# System_Power_Schematic.net
KiCad netlist of a schematic drawn in EAGLE
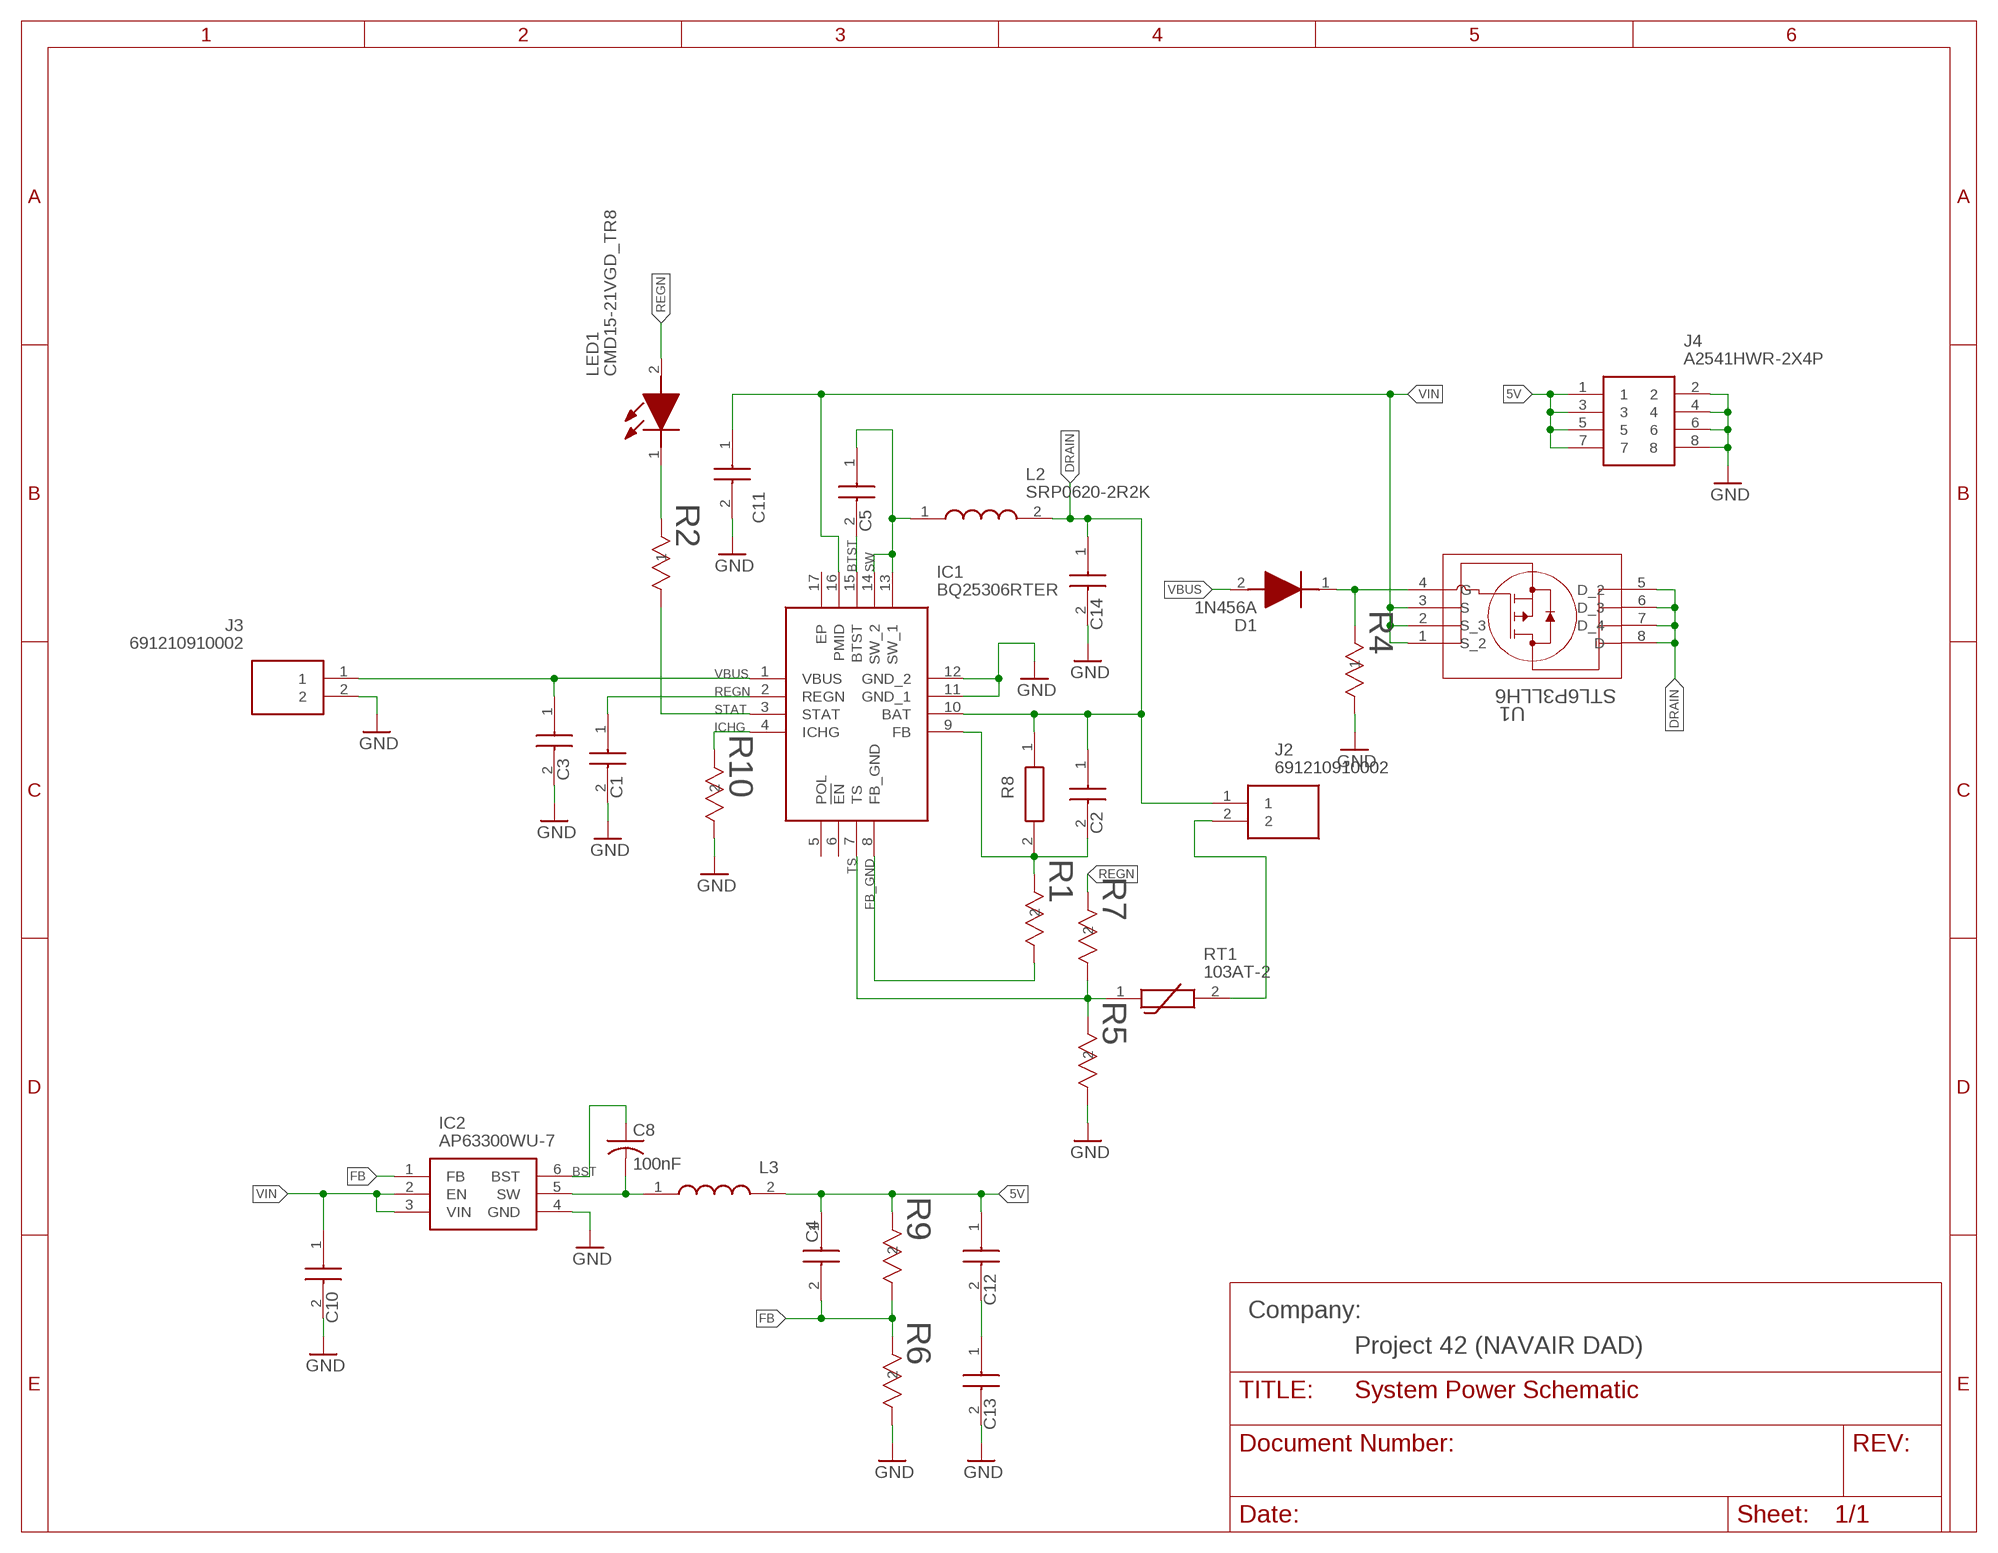
[diagram p0: schematic, sheet 1]

(export (version "E")
  (design (tool "Eeschema 10.0.6"))
  (components
    (comp (ref "C1")
      (value "TMK107ABJ225KA-T")
      (footprint "eagle-import:CAPC1608X90N")
      (fields (field (name "MOUSER_PART_NUMBER") "963-TMK107ABJ225KA-T"))
      (libsource (lib "eagle-import") (part "TMK107ABJ225KA-T"))
    )
    (comp (ref "C2")
      (value "CGA1A2X7R1H471K030BA")
      (footprint "eagle-import:CAPC1608X90N")
      (fields (field (name "MOUSER_PART_NUMBER") "810-CGA1A2X7R1H471KA"))
      (libsource (lib "eagle-import") (part "CGA1A2X7R1H471K030BA"))
    )
    (comp (ref "C3")
      (value "TMK107ABJ225KA-T")
      (footprint "eagle-import:CAPC1608X90N")
      (fields (field (name "MOUSER_PART_NUMBER") "963-TMK107ABJ225KA-T"))
      (libsource (lib "eagle-import") (part "TMK107ABJ225KA-T"))
    )
    (comp (ref "C4")
      (value "CL05C470JB5NNNC")
      (footprint "eagle-import:CAPC1005X55N")
      (fields (field (name "MOUSER_PART_NUMBER") "187-CL05C470JB5NNNC"))
      (libsource (lib "eagle-import") (part "CL05C470JB5NNNC"))
    )
    (comp (ref "C5")
      (value "885012107018")
      (footprint "eagle-import:CAPC2012X145N")
      (fields (field (name "MOUSER_PART_NUMBER") "710-885012107018"))
      (libsource (lib "eagle-import") (part "885012107018"))
    )
    (comp (ref "C8")
      (value "100nF")
      (footprint "eagle-import:C0805")
      (libsource (lib "eagle-import") (part "C-USC0805"))
    )
    (comp (ref "C10")
      (value "CL21A106KAYNNNG")
      (footprint "eagle-import:CAPC2012X145N")
      (fields (field (name "MOUSER_PART_NUMBER") "187-CL21A106KAYNNNG"))
      (libsource (lib "eagle-import") (part "CL21A106KAYNNNG"))
    )
    (comp (ref "C11")
      (value "CL21A106KAYNNNG")
      (footprint "eagle-import:CAPC2012X145N")
      (fields (field (name "MOUSER_PART_NUMBER") "187-CL21A106KAYNNNG"))
      (libsource (lib "eagle-import") (part "CL21A106KAYNNNG"))
    )
    (comp (ref "C12")
      (value "CL31A226KAHNNNE")
      (footprint "eagle-import:CAPC3216X180N")
      (fields (field (name "MOUSER_PART_NUMBER") "187-CL31A226KAHNNNE"))
      (libsource (lib "eagle-import") (part "CL31A226KAHNNNE"))
    )
    (comp (ref "C13")
      (value "CL31A226KAHNNNE")
      (footprint "eagle-import:CAPC3216X180N")
      (fields (field (name "MOUSER_PART_NUMBER") "187-CL31A226KAHNNNE"))
      (libsource (lib "eagle-import") (part "CL31A226KAHNNNE"))
    )
    (comp (ref "C14")
      (value "CL21A106KAYNNNG")
      (footprint "eagle-import:CAPC2012X145N")
      (fields (field (name "MOUSER_PART_NUMBER") "187-CL21A106KAYNNNG"))
      (libsource (lib "eagle-import") (part "CL21A106KAYNNNG"))
    )
    (comp (ref "D1")
      (value "1N456A")
      (footprint "eagle-import:DIO_1N456A")
      (fields (field (name "MOUSER_PART_NUMBER") "512-1N456A"))
      (libsource (lib "eagle-import") (part "1N456A"))
    )
    (comp (ref "IC1")
      (value "BQ25306RTER")
      (footprint "eagle-import:QFN50P300X300X80-17N")
      (fields (field (name "MOUSER_PART_NUMBER") "595-BQ25306RTER"))
      (libsource (lib "eagle-import") (part "BQ25306RTER"))
    )
    (comp (ref "IC2")
      (value "AP63300WU-7")
      (footprint "eagle-import:SOT95P280X90-6N")
      (fields (field (name "MOUSER_PART_NUMBER") "621-AP63300WU-7"))
      (libsource (lib "eagle-import") (part "AP63300WU-7"))
    )
    (comp (ref "J2")
      (value "691210910002")
      (footprint "eagle-import:691210910002")
      (fields (field (name "MOUSER_PART_NUMBER") "710-691210910002"))
      (libsource (lib "eagle-import") (part "691210910002"))
    )
    (comp (ref "J3")
      (value "691210910002")
      (footprint "eagle-import:691210910002")
      (fields (field (name "MOUSER_PART_NUMBER") "710-691210910002"))
      (libsource (lib "eagle-import") (part "691210910002"))
    )
    (comp (ref "J4")
      (value "A2541HWR-2X4P")
      (footprint "eagle-import:RHDRRA8W64P254_2X4_1066X850X52")
      (fields (field (name "MANUFACTURER_PART_NUMBER") "A2541HWR-2x4P"))
      (libsource (lib "eagle-import") (part "A2541HWR-2X4P"))
    )
    (comp (ref "L2")
      (value "SRP0620-2R2K")
      (footprint "eagle-import:SRP06202R2K")
      (fields (field (name "MOUSER_PART_NUMBER") "652-SRP0620-2R2K"))
      (libsource (lib "eagle-import") (part "SRP0620-2R2K"))
    )
    (comp (ref "L3")
      (value "SRP0615-6R8K")
      (footprint "eagle-import:SRP06152R2K")
      (fields (field (name "MOUSER_PART_NUMBER") "652-SRP0615-6R8K"))
      (libsource (lib "eagle-import") (part "SRP0615-6R8K"))
    )
    (comp (ref "LED1")
      (value "CMD15-21VGD_TR8")
      (footprint "eagle-import:LEDC3215X130N")
      (fields
        (field (name "ARROW_PART_NUMBER") "CMD15-21VGD/TR8")
        (field (name "MOUSER_PART_NUMBER") "606-CMD15-21VGD/TR8")
      )
      (libsource (lib "eagle-import") (part "CMD15-21VGD_TR8"))
    )
    (comp (ref "R1")
      (value "ERA-3AEB204V")
      (footprint "eagle-import:RC0603N_PAN")
      (fields (field (name "COPYRIGHT") "Copyright (C) 2023 Ultra Librarian. All rights reserved."))
      (libsource (lib "eagle-import") (part "ERA-3AEB204V"))
    )
    (comp (ref "R2")
      (value "RNCP0603FTD1K00")
      (footprint "eagle-import:STA_RNCP0603_STP")
      (fields (field (name "COPYRIGHT") "Copyright (C) 2023 Ultra Librarian. All rights reserved."))
      (libsource (lib "eagle-import") (part "RNCP0603FTD1K00"))
    )
    (comp (ref "R4")
      (value "PNM0603E5001BST5")
      (footprint "eagle-import:0603_VIS")
      (fields (field (name "COPYRIGHT") "Copyright (C) 2023 Ultra Librarian. All rights reserved."))
      (libsource (lib "eagle-import") (part "PNM0603E5001BST5"))
    )
    (comp (ref "R5")
      (value "RC0603FR-0712K4L")
      (footprint "eagle-import:RC0603N_YAG")
      (fields (field (name "COPYRIGHT") "Copyright (C) 2023 Ultra Librarian. All rights reserved."))
      (libsource (lib "eagle-import") (part "RC0603FR-0712K4L"))
    )
    (comp (ref "R6")
      (value "RC0603FR-0730K1L")
      (footprint "eagle-import:RC0603N_YAG")
      (fields (field (name "COPYRIGHT") "Copyright (C) 2023 Ultra Librarian. All rights reserved."))
      (libsource (lib "eagle-import") (part "RC0603FR-0730K1L"))
    )
    (comp (ref "R7")
      (value "RC0603FR-073K48L")
      (footprint "eagle-import:RC0603N_YAG")
      (fields (field (name "COPYRIGHT") "Copyright (C) 2023 Ultra Librarian. All rights reserved."))
      (libsource (lib "eagle-import") (part "RC0603FR-073K48L"))
    )
    (comp (ref "R8")
      (value "RK73H1JTTD1334F")
      (footprint "eagle-import:RESC1608X55N")
      (libsource (lib "eagle-import") (part "RK73H1JTTD1334F"))
    )
    (comp (ref "R9")
      (value "RC0603FR-07158KL")
      (footprint "eagle-import:RC0603N_YAG")
      (fields (field (name "COPYRIGHT") "Copyright (C) 2023 Ultra Librarian. All rights reserved."))
      (libsource (lib "eagle-import") (part "RC0603FR-07158KL"))
    )
    (comp (ref "R10")
      (value "RN73C1J13K3BTDF")
      (footprint "eagle-import:RES0603_RN73_TYCO_TYC")
      (fields (field (name "COPYRIGHT") "Copyright (C) 2023 Ultra Librarian. All rights reserved."))
      (libsource (lib "eagle-import") (part "RN73C1J13K3BTDF"))
    )
    (comp (ref "RT1")
      (value "103AT-2")
      (footprint "eagle-import:103AT2")
      (fields (field (name "MOUSER_PART_NUMBER") "954-103AT-2"))
      (libsource (lib "eagle-import") (part "103AT-2"))
    )
    (comp (ref "U1")
      (value "STL6P3LLH6")
      (footprint "eagle-import:POWERFLAT_3P3X3P3_STM")
      (fields (field (name "COPYRIGHT") "Copyright (C) 2023 Ultra Librarian. All rights reserved."))
      (libsource (lib "eagle-import") (part "STL6P3LLH6"))
    )
  )
  (nets
    (net (code "1") (name "/BST") (class "Default")
      (node (ref "C8") (pin "1") (pinfunction "1_1") (pintype "passive"))
      (node (ref "IC2") (pin "6") (pinfunction "BST_6") (pintype "bidirectional"))
    )
    (net (code "2") (name "/BTST") (class "Default")
      (node (ref "C5") (pin "2") (pinfunction "2_2") (pintype "bidirectional"))
      (node (ref "IC1") (pin "15") (pinfunction "BTST_15") (pintype "bidirectional"))
    )
    (net (code "3") (name "/FB_GND") (class "Default")
      (node (ref "IC1") (pin "8") (pinfunction "FB_GND_8") (pintype "bidirectional"))
      (node (ref "R1") (pin "1") (pinfunction "1_1") (pintype "passive"))
    )
    (net (code "4") (name "/ICHG") (class "Default")
      (node (ref "IC1") (pin "4") (pinfunction "ICHG_4") (pintype "bidirectional"))
      (node (ref "R10") (pin "2") (pinfunction "2_2") (pintype "passive"))
    )
    (net (code "5") (name "/STAT") (class "Default")
      (node (ref "IC1") (pin "3") (pinfunction "STAT_3") (pintype "bidirectional"))
      (node (ref "R2") (pin "2") (pinfunction "2_2") (pintype "passive"))
    )
    (net (code "6") (name "/SW") (class "Default")
      (node (ref "C5") (pin "1") (pinfunction "1_1") (pintype "bidirectional"))
      (node (ref "IC1") (pin "13") (pinfunction "SW_1_13") (pintype "bidirectional"))
      (node (ref "IC1") (pin "14") (pinfunction "SW_2_14") (pintype "bidirectional"))
      (node (ref "L2") (pin "1") (pinfunction "1_1") (pintype "bidirectional"))
    )
    (net (code "7") (name "/TS") (class "Default")
      (node (ref "IC1") (pin "7") (pinfunction "TS_7") (pintype "bidirectional"))
      (node (ref "R5") (pin "2") (pinfunction "2_2") (pintype "passive"))
      (node (ref "R7") (pin "1") (pinfunction "1_1") (pintype "passive"))
      (node (ref "RT1") (pin "1") (pinfunction "1_1") (pintype "bidirectional"))
    )
    (net (code "8") (name "5V") (class "Default")
      (node (ref "C12") (pin "1") (pinfunction "1_1") (pintype "bidirectional"))
      (node (ref "C4") (pin "1") (pinfunction "1_1") (pintype "bidirectional"))
      (node (ref "J4") (pin "1") (pinfunction "1_1") (pintype "bidirectional"))
      (node (ref "J4") (pin "3") (pinfunction "3_3") (pintype "bidirectional"))
      (node (ref "J4") (pin "5") (pinfunction "5_5") (pintype "bidirectional"))
      (node (ref "J4") (pin "7") (pinfunction "7_7") (pintype "bidirectional"))
      (node (ref "L3") (pin "2") (pinfunction "2_2") (pintype "bidirectional"))
      (node (ref "R9") (pin "2") (pinfunction "2_2") (pintype "passive"))
    )
    (net (code "9") (name "DRAIN") (class "Default")
      (node (ref "C14") (pin "1") (pinfunction "1_1") (pintype "bidirectional"))
      (node (ref "C2") (pin "1") (pinfunction "1_1") (pintype "bidirectional"))
      (node (ref "IC1") (pin "10") (pinfunction "BAT_10") (pintype "bidirectional"))
      (node (ref "J2") (pin "1") (pinfunction "1_1") (pintype "bidirectional"))
      (node (ref "L2") (pin "2") (pinfunction "2_2") (pintype "bidirectional"))
      (node (ref "R8") (pin "1") (pinfunction "1_1") (pintype "bidirectional"))
      (node (ref "U1") (pin "5") (pinfunction "D_2_5") (pintype "passive"))
      (node (ref "U1") (pin "6") (pinfunction "D_3_6") (pintype "passive"))
      (node (ref "U1") (pin "7") (pinfunction "D_4_7") (pintype "passive"))
      (node (ref "U1") (pin "8") (pinfunction "D_8") (pintype "passive"))
    )
    (net (code "10") (name "FB") (class "Default")
      (node (ref "C4") (pin "2") (pinfunction "2_2") (pintype "bidirectional"))
      (node (ref "IC2") (pin "1") (pinfunction "FB_1") (pintype "bidirectional"))
      (node (ref "R6") (pin "2") (pinfunction "2_2") (pintype "passive"))
      (node (ref "R9") (pin "1") (pinfunction "1_1") (pintype "passive"))
    )
    (net (code "11") (name "GND") (class "Default")
      (node (ref "C1") (pin "2") (pinfunction "2_2") (pintype "bidirectional"))
      (node (ref "C10") (pin "2") (pinfunction "2_2") (pintype "bidirectional"))
      (node (ref "C11") (pin "2") (pinfunction "2_2") (pintype "bidirectional"))
      (node (ref "C13") (pin "2") (pinfunction "2_2") (pintype "bidirectional"))
      (node (ref "C14") (pin "2") (pinfunction "2_2") (pintype "bidirectional"))
      (node (ref "C3") (pin "2") (pinfunction "2_2") (pintype "bidirectional"))
      (node (ref "IC1") (pin "11") (pinfunction "GND_1_11") (pintype "bidirectional"))
      (node (ref "IC1") (pin "12") (pinfunction "GND_2_12") (pintype "bidirectional"))
      (node (ref "IC2") (pin "4") (pinfunction "GND_4") (pintype "bidirectional"))
      (node (ref "J3") (pin "2") (pinfunction "2_2") (pintype "bidirectional"))
      (node (ref "J4") (pin "2") (pinfunction "2_2") (pintype "bidirectional"))
      (node (ref "J4") (pin "4") (pinfunction "4_4") (pintype "bidirectional"))
      (node (ref "J4") (pin "6") (pinfunction "6_6") (pintype "bidirectional"))
      (node (ref "J4") (pin "8") (pinfunction "8_8") (pintype "bidirectional"))
      (node (ref "R10") (pin "1") (pinfunction "1_1") (pintype "passive"))
      (node (ref "R4") (pin "2") (pinfunction "2_2") (pintype "passive"))
      (node (ref "R5") (pin "1") (pinfunction "1_1") (pintype "passive"))
      (node (ref "R6") (pin "1") (pinfunction "1_1") (pintype "passive"))
    )
    (net (code "12") (name "Net-(C12-Pad2)") (class "Default")
      (node (ref "C12") (pin "2") (pinfunction "2_2") (pintype "bidirectional"))
      (node (ref "C13") (pin "1") (pinfunction "1_1") (pintype "bidirectional"))
    )
    (net (code "13") (name "Net-(D1-K)") (class "Default")
      (node (ref "D1") (pin "1") (pinfunction "K_1") (pintype "bidirectional"))
      (node (ref "R4") (pin "1") (pinfunction "1_1") (pintype "passive"))
      (node (ref "U1") (pin "4") (pinfunction "G_4") (pintype "passive"))
    )
    (net (code "14") (name "Net-(IC1-FB)") (class "Default")
      (node (ref "C2") (pin "2") (pinfunction "2_2") (pintype "bidirectional"))
      (node (ref "IC1") (pin "9") (pinfunction "FB_9") (pintype "bidirectional"))
      (node (ref "R1") (pin "2") (pinfunction "2_2") (pintype "passive"))
      (node (ref "R8") (pin "2") (pinfunction "2_2") (pintype "bidirectional"))
    )
    (net (code "15") (name "Net-(IC2-SW)") (class "Default")
      (node (ref "C8") (pin "2") (pinfunction "2_2") (pintype "passive"))
      (node (ref "IC2") (pin "5") (pinfunction "SW_5") (pintype "bidirectional"))
      (node (ref "L3") (pin "1") (pinfunction "1_1") (pintype "bidirectional"))
    )
    (net (code "16") (name "Net-(J2-Pad2)") (class "Default")
      (node (ref "J2") (pin "2") (pinfunction "2_2") (pintype "bidirectional"))
      (node (ref "RT1") (pin "2") (pinfunction "2_2") (pintype "bidirectional"))
    )
    (net (code "17") (name "Net-(LED1-K)") (class "Default")
      (node (ref "LED1") (pin "1") (pinfunction "K_1") (pintype "bidirectional"))
      (node (ref "R2") (pin "1") (pinfunction "1_1") (pintype "passive"))
    )
    (net (code "18") (name "REGN") (class "Default")
      (node (ref "C1") (pin "1") (pinfunction "1_1") (pintype "bidirectional"))
      (node (ref "IC1") (pin "2") (pinfunction "REGN_2") (pintype "bidirectional"))
      (node (ref "LED1") (pin "2") (pinfunction "A_2") (pintype "bidirectional"))
      (node (ref "R7") (pin "2") (pinfunction "2_2") (pintype "passive"))
    )
    (net (code "19") (name "VBUS") (class "Default")
      (node (ref "C3") (pin "1") (pinfunction "1_1") (pintype "bidirectional"))
      (node (ref "D1") (pin "2") (pinfunction "A_2") (pintype "bidirectional"))
      (node (ref "IC1") (pin "1") (pinfunction "VBUS_1") (pintype "bidirectional"))
      (node (ref "J3") (pin "1") (pinfunction "1_1") (pintype "bidirectional"))
    )
    (net (code "20") (name "VIN") (class "Default")
      (node (ref "C10") (pin "1") (pinfunction "1_1") (pintype "bidirectional"))
      (node (ref "C11") (pin "1") (pinfunction "1_1") (pintype "bidirectional"))
      (node (ref "IC1") (pin "16") (pinfunction "PMID_16") (pintype "bidirectional"))
      (node (ref "IC2") (pin "2") (pinfunction "EN_2") (pintype "bidirectional"))
      (node (ref "IC2") (pin "3") (pinfunction "VIN_3") (pintype "bidirectional"))
      (node (ref "U1") (pin "1") (pinfunction "S_2_1") (pintype "passive"))
      (node (ref "U1") (pin "2") (pinfunction "S_3_2") (pintype "passive"))
      (node (ref "U1") (pin "3") (pinfunction "S_3") (pintype "passive"))
    )
    (net (code "21") (name "unconnected-(IC1-EP-Pad17)") (class "Default")
      (node (ref "IC1") (pin "17") (pinfunction "EP_17") (pintype "bidirectional"))
    )
    (net (code "22") (name "unconnected-(IC1-POL-Pad5)") (class "Default")
      (node (ref "IC1") (pin "5") (pinfunction "POL_5") (pintype "bidirectional"))
    )
    (net (code "23") (name "unconnected-(IC1-~{EN}-Pad6)") (class "Default")
      (node (ref "IC1") (pin "6") (pinfunction "~{EN}_6") (pintype "bidirectional"))
    )
  )
)
